# PowerAmplifier915MHz.net
KiCad netlist of a schematic drawn in Altium Designer
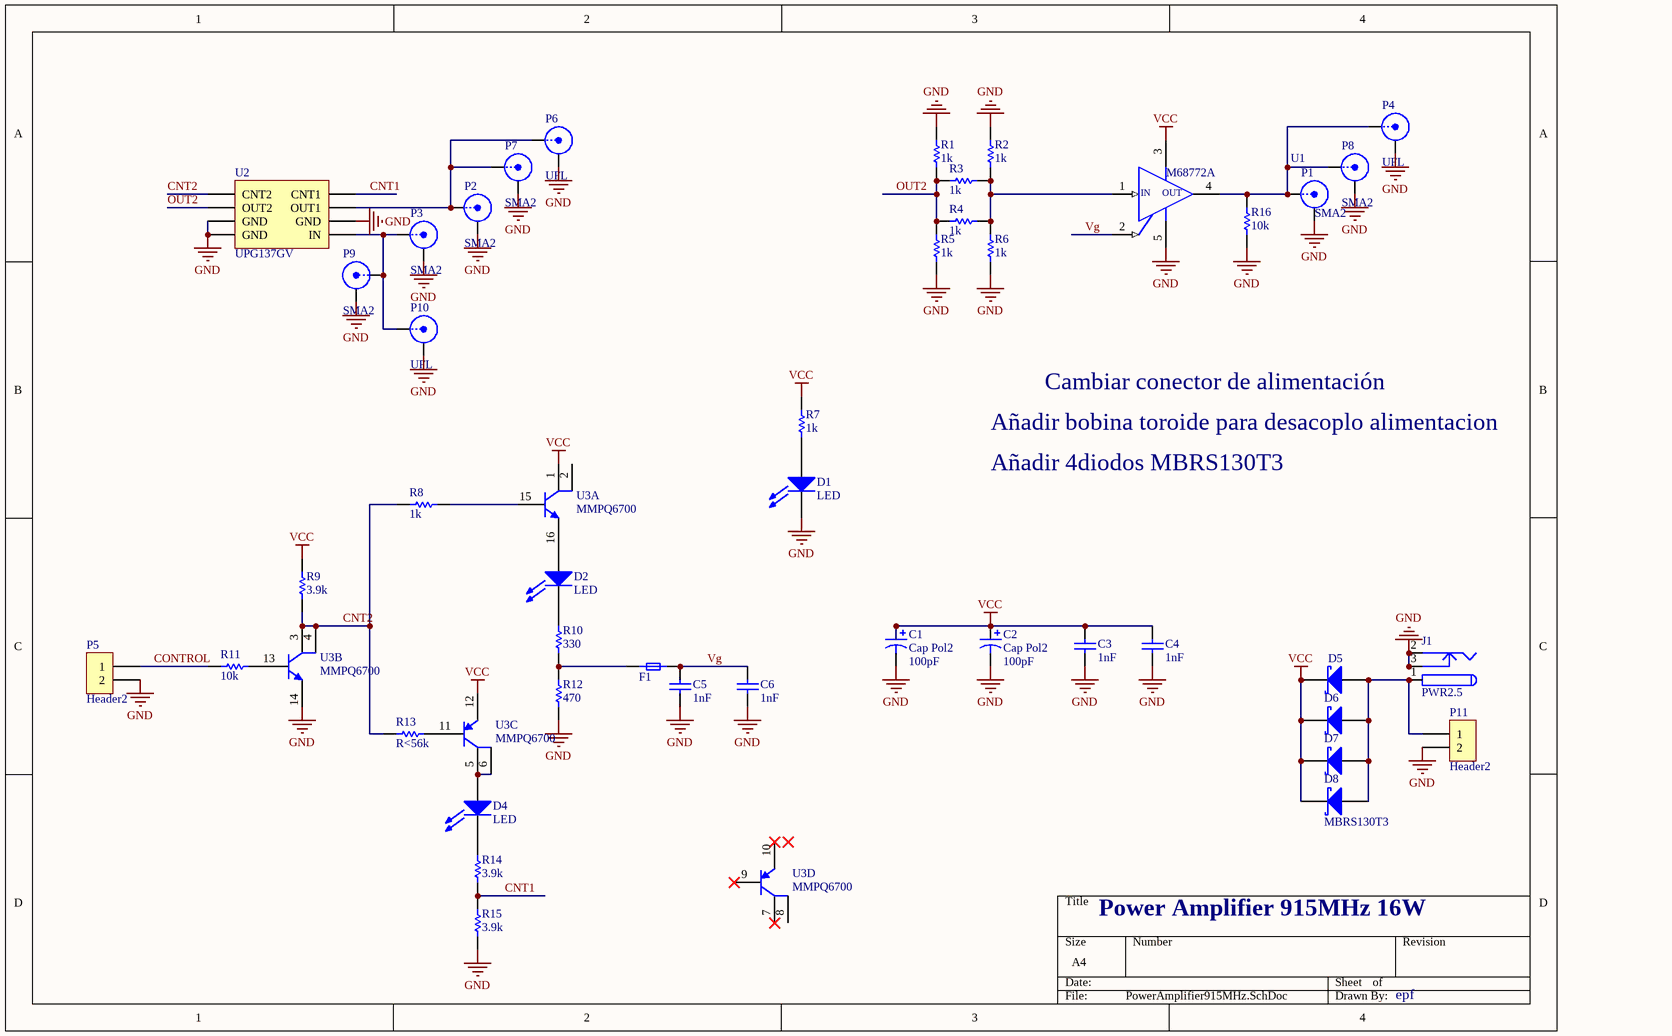
[diagram p0: PowerAmplifier915MHz.SchDoc]

(export (version "E")
  (design (tool "Eeschema 10.0.6"))
  (components
    (comp (ref "C1")
      (value "Cap Pol2")
      (footprint "TC7360-2924")
      (description "Polarized Capacitor (Axial)")
      (fields (field (name "ALTIUM_VALUE") "100pF") (field (name "PUBLISHER") "Altium Limited"))
      (libsource (lib "epf") (part "Cap Pol2"))
    )
    (comp (ref "C2")
      (value "Cap Pol2")
      (footprint "TC7360-2924")
      (description "Polarized Capacitor (Axial)")
      (fields (field (name "ALTIUM_VALUE") "100pF") (field (name "PUBLISHER") "Altium Limited"))
      (libsource (lib "epf") (part "Cap Pol2"))
    )
    (comp (ref "C3")
      (value "1nF")
      (footprint "0805_CAP")
      (fields (field (name "Comment") "Capacitor"))
      (libsource (lib "epf") (part "Cap"))
    )
    (comp (ref "C4")
      (value "1nF")
      (footprint "0805_CAP")
      (fields (field (name "Comment") "Capacitor"))
      (libsource (lib "epf") (part "Cap"))
    )
    (comp (ref "C5")
      (value "1nF")
      (footprint "0805_CAP")
      (fields (field (name "Comment") "Capacitor"))
      (libsource (lib "epf") (part "Cap"))
    )
    (comp (ref "C6")
      (value "1nF")
      (footprint "0805_CAP")
      (fields (field (name "Comment") "Capacitor"))
      (libsource (lib "epf") (part "Cap"))
    )
    (comp (ref "D1") (value "LED") (footprint "LED0603") (libsource (lib "epf") (part "LED1")))
    (comp (ref "D2") (value "LED") (footprint "LED0603") (libsource (lib "epf") (part "LED1")))
    (comp (ref "D4") (value "LED") (footprint "LED0603") (libsource (lib "epf") (part "LED1")))
    (comp (ref "D5")
      (value "MBRS130T3")
      (footprint "MBRS130T3")
      (description "DIODO 1A 30V")
      (libsource (lib "epf") (part "MBRS130T3"))
    )
    (comp (ref "D6")
      (value "MBRS130T3")
      (footprint "MBRS130T3")
      (description "DIODO 1A 30V")
      (libsource (lib "epf") (part "MBRS130T3"))
    )
    (comp (ref "D7")
      (value "MBRS130T3")
      (footprint "MBRS130T3")
      (description "DIODO 1A 30V")
      (libsource (lib "epf") (part "MBRS130T3"))
    )
    (comp (ref "D8")
      (value "MBRS130T3")
      (footprint "MBRS130T3")
      (description "DIODO 1A 30V")
      (libsource (lib "epf") (part "MBRS130T3"))
    )
    (comp (ref "F1") (value "Ferrita") (footprint "IND0603") (libsource (lib "epf") (part "Ferrita")))
    (comp (ref "J1")
      (value "PWR2.5")
      (footprint "KLD-0202")
      (description "Low Voltage Power Supply Connector")
      (fields (field (name "PUBLISHER") "Altium Limited"))
      (libsource (lib "epf") (part "PWR2.5"))
    )
    (comp (ref "P1")
      (value "SMA2")
      (footprint "SMAL_Antena")
      (description "BNC Elbow Connector")
      (fields (field (name "PUBLISHER") "Altium Limited"))
      (libsource (lib "epf") (part "SMA2"))
    )
    (comp (ref "P2")
      (value "SMA2")
      (footprint "SMAL_Antena")
      (description "BNC Elbow Connector")
      (fields (field (name "PUBLISHER") "Altium Limited"))
      (libsource (lib "epf") (part "SMA2"))
    )
    (comp (ref "P3")
      (value "SMA2")
      (footprint "SMAL22")
      (description "BNC Elbow Connector")
      (fields (field (name "PUBLISHER") "Altium Limited"))
      (libsource (lib "epf") (part "SMA2"))
    )
    (comp (ref "P4") (value "UFL") (footprint "UFL") (libsource (lib "epf") (part "UFL")))
    (comp (ref "P5") (value "Header2") (footprint "Header2Macho") (libsource (lib "") (part "Header2_1")))
    (comp (ref "P6") (value "UFL") (footprint "UFL") (libsource (lib "epf") (part "UFL")))
    (comp (ref "P7")
      (value "SMA2")
      (footprint "SMA-4HOLE")
      (description "BNC Elbow Connector")
      (fields (field (name "PUBLISHER") "Altium Limited"))
      (libsource (lib "epf") (part "SMA2"))
    )
    (comp (ref "P8")
      (value "SMA2")
      (footprint "SMA-4HOLE")
      (description "BNC Elbow Connector")
      (fields (field (name "PUBLISHER") "Altium Limited"))
      (libsource (lib "epf") (part "SMA2"))
    )
    (comp (ref "P9")
      (value "SMA2")
      (footprint "SMA-4HOLE")
      (description "BNC Elbow Connector")
      (fields (field (name "PUBLISHER") "Altium Limited"))
      (libsource (lib "epf") (part "SMA2"))
    )
    (comp (ref "P10") (value "UFL") (footprint "UFL") (libsource (lib "epf") (part "UFL")))
    (comp (ref "P11") (value "Header2") (footprint "Header2Macho") (libsource (lib "epf") (part "Header2")))
    (comp (ref "R1")
      (value "1k")
      (footprint "RES0805")
      (fields (field (name "Comment") "Resistor"))
      (libsource (lib "epf") (part "Res"))
    )
    (comp (ref "R2")
      (value "1k")
      (footprint "RES0805")
      (fields (field (name "Comment") "Resistor"))
      (libsource (lib "epf") (part "Res"))
    )
    (comp (ref "R3")
      (value "1k")
      (footprint "RES0805")
      (fields (field (name "Comment") "Resistor"))
      (libsource (lib "epf") (part "Res"))
    )
    (comp (ref "R4")
      (value "1k")
      (footprint "RES0805")
      (fields (field (name "Comment") "Resistor"))
      (libsource (lib "epf") (part "Res"))
    )
    (comp (ref "R5")
      (value "1k")
      (footprint "RES0805")
      (fields (field (name "Comment") "Resistor"))
      (libsource (lib "epf") (part "Res"))
    )
    (comp (ref "R6")
      (value "1k")
      (footprint "RES0805")
      (fields (field (name "Comment") "Resistor"))
      (libsource (lib "epf") (part "Res"))
    )
    (comp (ref "R7")
      (value "1k")
      (footprint "RES0805")
      (fields (field (name "Comment") "Resistor"))
      (libsource (lib "epf") (part "Res"))
    )
    (comp (ref "R8")
      (value "1k")
      (footprint "RES0805")
      (fields (field (name "Comment") "Resistor"))
      (libsource (lib "epf") (part "Res"))
    )
    (comp (ref "R9")
      (value "3.9k")
      (footprint "RES0805")
      (fields (field (name "Comment") "Resistor"))
      (libsource (lib "epf") (part "Res"))
    )
    (comp (ref "R10")
      (value "330")
      (footprint "RES0805")
      (fields (field (name "Comment") "Resistor"))
      (libsource (lib "epf") (part "Res"))
    )
    (comp (ref "R11")
      (value "10k")
      (footprint "RES0805")
      (fields (field (name "Comment") "Resistor"))
      (libsource (lib "epf") (part "Res"))
    )
    (comp (ref "R12")
      (value "470")
      (footprint "RES0805")
      (fields (field (name "Comment") "Resistor"))
      (libsource (lib "epf") (part "Res"))
    )
    (comp (ref "R13")
      (value "R<56k")
      (footprint "RES0805")
      (fields (field (name "Comment") "Resistor"))
      (libsource (lib "epf") (part "Res"))
    )
    (comp (ref "R14")
      (value "3.9k")
      (footprint "RES0805")
      (fields (field (name "Comment") "Resistor"))
      (libsource (lib "epf") (part "Res"))
    )
    (comp (ref "R15")
      (value "3.9k")
      (footprint "RES0805")
      (fields (field (name "Comment") "Resistor"))
      (libsource (lib "epf") (part "Res"))
    )
    (comp (ref "R16")
      (value "10k")
      (footprint "RES0805")
      (fields (field (name "Comment") "Resistor"))
      (libsource (lib "epf") (part "Res"))
    )
    (comp (ref "U1")
      (value "M68772A")
      (footprint "M68772A")
      (description "AMPLIFICADOR DE POTENCIA 915MHz")
      (libsource (lib "epf") (part "M68772A"))
    )
    (comp (ref "U2")
      (value "UPG137GV")
      (footprint "SOP65P640-8L")
      (description "L-Band SPDT GaAs MMIC SWITCH")
      (libsource (lib "epf") (part "UPG137GV"))
    )
    (comp (ref "U3")
      (value "MMPQ6700")
      (footprint "SOIC127P602-16BN")
      (description "Quad NPN & PNP General Purpose Amplifier")
      (libsource (lib "epf") (part "MMPQ6700"))
    )
  )
  (nets
    (net (code "1") (name "/CNT1") (class "Default")
      (node (ref "R14") (pin "1") (pinfunction "1_1") (pintype "passive"))
      (node (ref "R15") (pin "2") (pinfunction "2_2") (pintype "passive"))
      (node (ref "U2") (pin "8") (pinfunction "CNT1_8") (pintype "passive"))
    )
    (net (code "2") (name "/CNT2") (class "Default")
      (node (ref "R13") (pin "1") (pinfunction "1_1") (pintype "passive"))
      (node (ref "R8") (pin "1") (pinfunction "1_1") (pintype "passive"))
      (node (ref "R9") (pin "1") (pinfunction "1_1") (pintype "passive"))
      (node (ref "U2") (pin "1") (pinfunction "CNT2_1") (pintype "passive"))
      (node (ref "U3") (pin "3") (pinfunction "C_3") (pintype "passive"))
      (node (ref "U3") (pin "4") (pinfunction "C_4") (pintype "passive"))
    )
    (net (code "3") (name "/CONTROL") (class "Default")
      (node (ref "P5") (pin "1") (pinfunction "1_1") (pintype "passive"))
      (node (ref "R11") (pin "1") (pinfunction "1_1") (pintype "passive"))
    )
    (net (code "4") (name "/OUT2") (class "Default")
      (node (ref "R1") (pin "2") (pinfunction "2_2") (pintype "passive"))
      (node (ref "R3") (pin "1") (pinfunction "1_1") (pintype "passive"))
      (node (ref "R4") (pin "1") (pinfunction "1_1") (pintype "passive"))
      (node (ref "R5") (pin "1") (pinfunction "1_1") (pintype "passive"))
      (node (ref "U2") (pin "2") (pinfunction "OUT2_2") (pintype "passive"))
    )
    (net (code "5") (name "/Vg") (class "Default")
      (node (ref "C5") (pin "2") (pinfunction "2_2") (pintype "passive"))
      (node (ref "C6") (pin "2") (pinfunction "2_2") (pintype "passive"))
      (node (ref "F1") (pin "2") (pinfunction "2_2") (pintype "passive"))
      (node (ref "U1") (pin "2") (pinfunction "Vgg_2") (pintype "input"))
    )
    (net (code "6") (name "GND") (class "Default")
      (node (ref "C1") (pin "2") (pinfunction "2_2") (pintype "passive"))
      (node (ref "C2") (pin "2") (pinfunction "2_2") (pintype "passive"))
      (node (ref "C3") (pin "1") (pinfunction "1_1") (pintype "passive"))
      (node (ref "C4") (pin "1") (pinfunction "1_1") (pintype "passive"))
      (node (ref "C5") (pin "1") (pinfunction "1_1") (pintype "passive"))
      (node (ref "C6") (pin "1") (pinfunction "1_1") (pintype "passive"))
      (node (ref "D1") (pin "2") (pinfunction "K_2") (pintype "passive"))
      (node (ref "J1") (pin "2") (pinfunction "2_2") (pintype "power_in"))
      (node (ref "J1") (pin "2A") (pinfunction "2A_2A") (pintype "power_in"))
      (node (ref "J1") (pin "2B") (pinfunction "2B_2B") (pintype "power_in"))
      (node (ref "J1") (pin "3") (pinfunction "3_3") (pintype "power_in"))
      (node (ref "J1") (pin "3A") (pinfunction "3A_3A") (pintype "power_in"))
      (node (ref "J1") (pin "3B") (pinfunction "3B_3B") (pintype "power_in"))
      (node (ref "P1") (pin "0") (pinfunction "Y_0") (pintype "passive"))
      (node (ref "P10") (pin "2") (pinfunction "Y_2") (pintype "passive"))
      (node (ref "P11") (pin "2") (pinfunction "2_2") (pintype "passive"))
      (node (ref "P2") (pin "0") (pinfunction "Y_0") (pintype "passive"))
      (node (ref "P3") (pin "0") (pinfunction "Y_0") (pintype "passive"))
      (node (ref "P4") (pin "2") (pinfunction "Y_2") (pintype "passive"))
      (node (ref "P5") (pin "2") (pinfunction "2_2") (pintype "passive"))
      (node (ref "P6") (pin "2") (pinfunction "Y_2") (pintype "passive"))
      (node (ref "P7") (pin "0") (pinfunction "Y_0") (pintype "passive"))
      (node (ref "P8") (pin "0") (pinfunction "Y_0") (pintype "passive"))
      (node (ref "P9") (pin "0") (pinfunction "Y_0") (pintype "passive"))
      (node (ref "R1") (pin "1") (pinfunction "1_1") (pintype "passive"))
      (node (ref "R12") (pin "1") (pinfunction "1_1") (pintype "passive"))
      (node (ref "R15") (pin "1") (pinfunction "1_1") (pintype "passive"))
      (node (ref "R16") (pin "2") (pinfunction "2_2") (pintype "passive"))
      (node (ref "R2") (pin "1") (pinfunction "1_1") (pintype "passive"))
      (node (ref "R5") (pin "2") (pinfunction "2_2") (pintype "passive"))
      (node (ref "R6") (pin "2") (pinfunction "2_2") (pintype "passive"))
      (node (ref "U1") (pin "5") (pinfunction "GND_5") (pintype "power_in"))
      (node (ref "U2") (pin "3") (pinfunction "GND_3") (pintype "passive"))
      (node (ref "U2") (pin "4") (pinfunction "GND_4") (pintype "passive"))
      (node (ref "U2") (pin "6") (pinfunction "GND_6") (pintype "passive"))
      (node (ref "U3") (pin "14") (pinfunction "E_14") (pintype "passive"))
    )
    (net (code "7") (name "Net-(D1-A)") (class "Default")
      (node (ref "D1") (pin "1") (pinfunction "A_1") (pintype "passive"))
      (node (ref "R7") (pin "1") (pinfunction "1_1") (pintype "passive"))
    )
    (net (code "8") (name "Net-(D2-A)") (class "Default")
      (node (ref "D2") (pin "1") (pinfunction "A_1") (pintype "passive"))
      (node (ref "U3") (pin "16") (pinfunction "E_16") (pintype "passive"))
    )
    (net (code "9") (name "Net-(D2-K)") (class "Default")
      (node (ref "D2") (pin "2") (pinfunction "K_2") (pintype "passive"))
      (node (ref "R10") (pin "2") (pinfunction "2_2") (pintype "passive"))
    )
    (net (code "10") (name "Net-(D4-A)") (class "Default")
      (node (ref "D4") (pin "1") (pinfunction "A_1") (pintype "passive"))
      (node (ref "U3") (pin "5") (pinfunction "C_5") (pintype "passive"))
      (node (ref "U3") (pin "6") (pinfunction "C_6") (pintype "passive"))
    )
    (net (code "11") (name "Net-(D4-K)") (class "Default")
      (node (ref "D4") (pin "2") (pinfunction "K_2") (pintype "passive"))
      (node (ref "R14") (pin "2") (pinfunction "2_2") (pintype "passive"))
    )
    (net (code "12") (name "Net-(D5-A)") (class "Default")
      (node (ref "D5") (pin "1") (pinfunction "A_1") (pintype "passive"))
      (node (ref "D6") (pin "1") (pinfunction "A_1") (pintype "passive"))
      (node (ref "D7") (pin "1") (pinfunction "A_1") (pintype "passive"))
      (node (ref "D8") (pin "1") (pinfunction "A_1") (pintype "passive"))
      (node (ref "J1") (pin "1") (pinfunction "1_1") (pintype "power_in"))
      (node (ref "J1") (pin "1A") (pinfunction "1A_1A") (pintype "power_in"))
      (node (ref "J1") (pin "1B") (pinfunction "1B_1B") (pintype "power_in"))
      (node (ref "P11") (pin "1") (pinfunction "1_1") (pintype "passive"))
    )
    (net (code "13") (name "Net-(F1-Pad1)") (class "Default")
      (node (ref "F1") (pin "1") (pinfunction "1_1") (pintype "passive"))
      (node (ref "R10") (pin "1") (pinfunction "1_1") (pintype "passive"))
      (node (ref "R12") (pin "2") (pinfunction "2_2") (pintype "passive"))
    )
    (net (code "14") (name "Net-(P1-X)") (class "Default")
      (node (ref "P1") (pin "1") (pinfunction "X_1") (pintype "passive"))
      (node (ref "P4") (pin "1") (pinfunction "X_1") (pintype "passive"))
      (node (ref "P8") (pin "1") (pinfunction "X_1") (pintype "passive"))
      (node (ref "R16") (pin "1") (pinfunction "1_1") (pintype "passive"))
      (node (ref "U1") (pin "4") (pinfunction "OUT_4") (pintype "power_in"))
    )
    (net (code "15") (name "Net-(P2-X)") (class "Default")
      (node (ref "P2") (pin "1") (pinfunction "X_1") (pintype "passive"))
      (node (ref "P6") (pin "1") (pinfunction "X_1") (pintype "passive"))
      (node (ref "P7") (pin "1") (pinfunction "X_1") (pintype "passive"))
      (node (ref "U2") (pin "7") (pinfunction "OUT1_7") (pintype "passive"))
    )
    (net (code "16") (name "Net-(P10-X)") (class "Default")
      (node (ref "P10") (pin "1") (pinfunction "X_1") (pintype "passive"))
      (node (ref "P3") (pin "1") (pinfunction "X_1") (pintype "passive"))
      (node (ref "P9") (pin "1") (pinfunction "X_1") (pintype "passive"))
      (node (ref "U2") (pin "5") (pinfunction "IN_5") (pintype "passive"))
    )
    (net (code "17") (name "Net-(U1-IN)") (class "Default")
      (node (ref "R2") (pin "2") (pinfunction "2_2") (pintype "passive"))
      (node (ref "R3") (pin "2") (pinfunction "2_2") (pintype "passive"))
      (node (ref "R4") (pin "2") (pinfunction "2_2") (pintype "passive"))
      (node (ref "R6") (pin "1") (pinfunction "1_1") (pintype "passive"))
      (node (ref "U1") (pin "1") (pinfunction "IN_1") (pintype "input"))
    )
    (net (code "18") (name "Net-(U3A-B)") (class "Default")
      (node (ref "R8") (pin "2") (pinfunction "2_2") (pintype "passive"))
      (node (ref "U3") (pin "15") (pinfunction "B_15") (pintype "passive"))
    )
    (net (code "19") (name "Net-(U3B-B)") (class "Default")
      (node (ref "R11") (pin "2") (pinfunction "2_2") (pintype "passive"))
      (node (ref "U3") (pin "13") (pinfunction "B_13") (pintype "passive"))
    )
    (net (code "20") (name "Net-(U3C-B)") (class "Default")
      (node (ref "R13") (pin "2") (pinfunction "2_2") (pintype "passive"))
      (node (ref "U3") (pin "11") (pinfunction "B_11") (pintype "passive"))
    )
    (net (code "21") (name "VCC") (class "Default")
      (node (ref "C1") (pin "1") (pinfunction "1_1") (pintype "passive"))
      (node (ref "C2") (pin "1") (pinfunction "1_1") (pintype "passive"))
      (node (ref "C3") (pin "2") (pinfunction "2_2") (pintype "passive"))
      (node (ref "C4") (pin "2") (pinfunction "2_2") (pintype "passive"))
      (node (ref "D5") (pin "2") (pinfunction "K_2") (pintype "passive"))
      (node (ref "D6") (pin "2") (pinfunction "K_2") (pintype "passive"))
      (node (ref "D7") (pin "2") (pinfunction "K_2") (pintype "passive"))
      (node (ref "D8") (pin "2") (pinfunction "K_2") (pintype "passive"))
      (node (ref "R7") (pin "2") (pinfunction "2_2") (pintype "passive"))
      (node (ref "R9") (pin "2") (pinfunction "2_2") (pintype "passive"))
      (node (ref "U1") (pin "3") (pinfunction "Vdd_3") (pintype "power_in"))
      (node (ref "U3") (pin "1") (pinfunction "C_1") (pintype "passive"))
      (node (ref "U3") (pin "12") (pinfunction "E_12") (pintype "passive"))
    )
    (net (code "22") (name "unconnected-(U3A-C-Pad2)") (class "Default")
      (node (ref "U3") (pin "2") (pinfunction "C_2") (pintype "passive"))
    )
    (net (code "23") (name "unconnected-(U3D-B-Pad9)") (class "Default")
      (node (ref "U3") (pin "9") (pinfunction "B_9") (pintype "passive+no_connect"))
    )
    (net (code "24") (name "unconnected-(U3D-C-Pad7)") (class "Default")
      (node (ref "U3") (pin "7") (pinfunction "C_7") (pintype "passive+no_connect"))
    )
    (net (code "25") (name "unconnected-(U3D-C-Pad8)") (class "Default")
      (node (ref "U3") (pin "8") (pinfunction "C_8") (pintype "passive"))
    )
    (net (code "26") (name "unconnected-(U3D-E-Pad10)") (class "Default")
      (node (ref "U3") (pin "10") (pinfunction "E_10") (pintype "passive+no_connect"))
    )
  )
)
